# Group_03.net
KiCad netlist of a schematic drawn in EAGLE
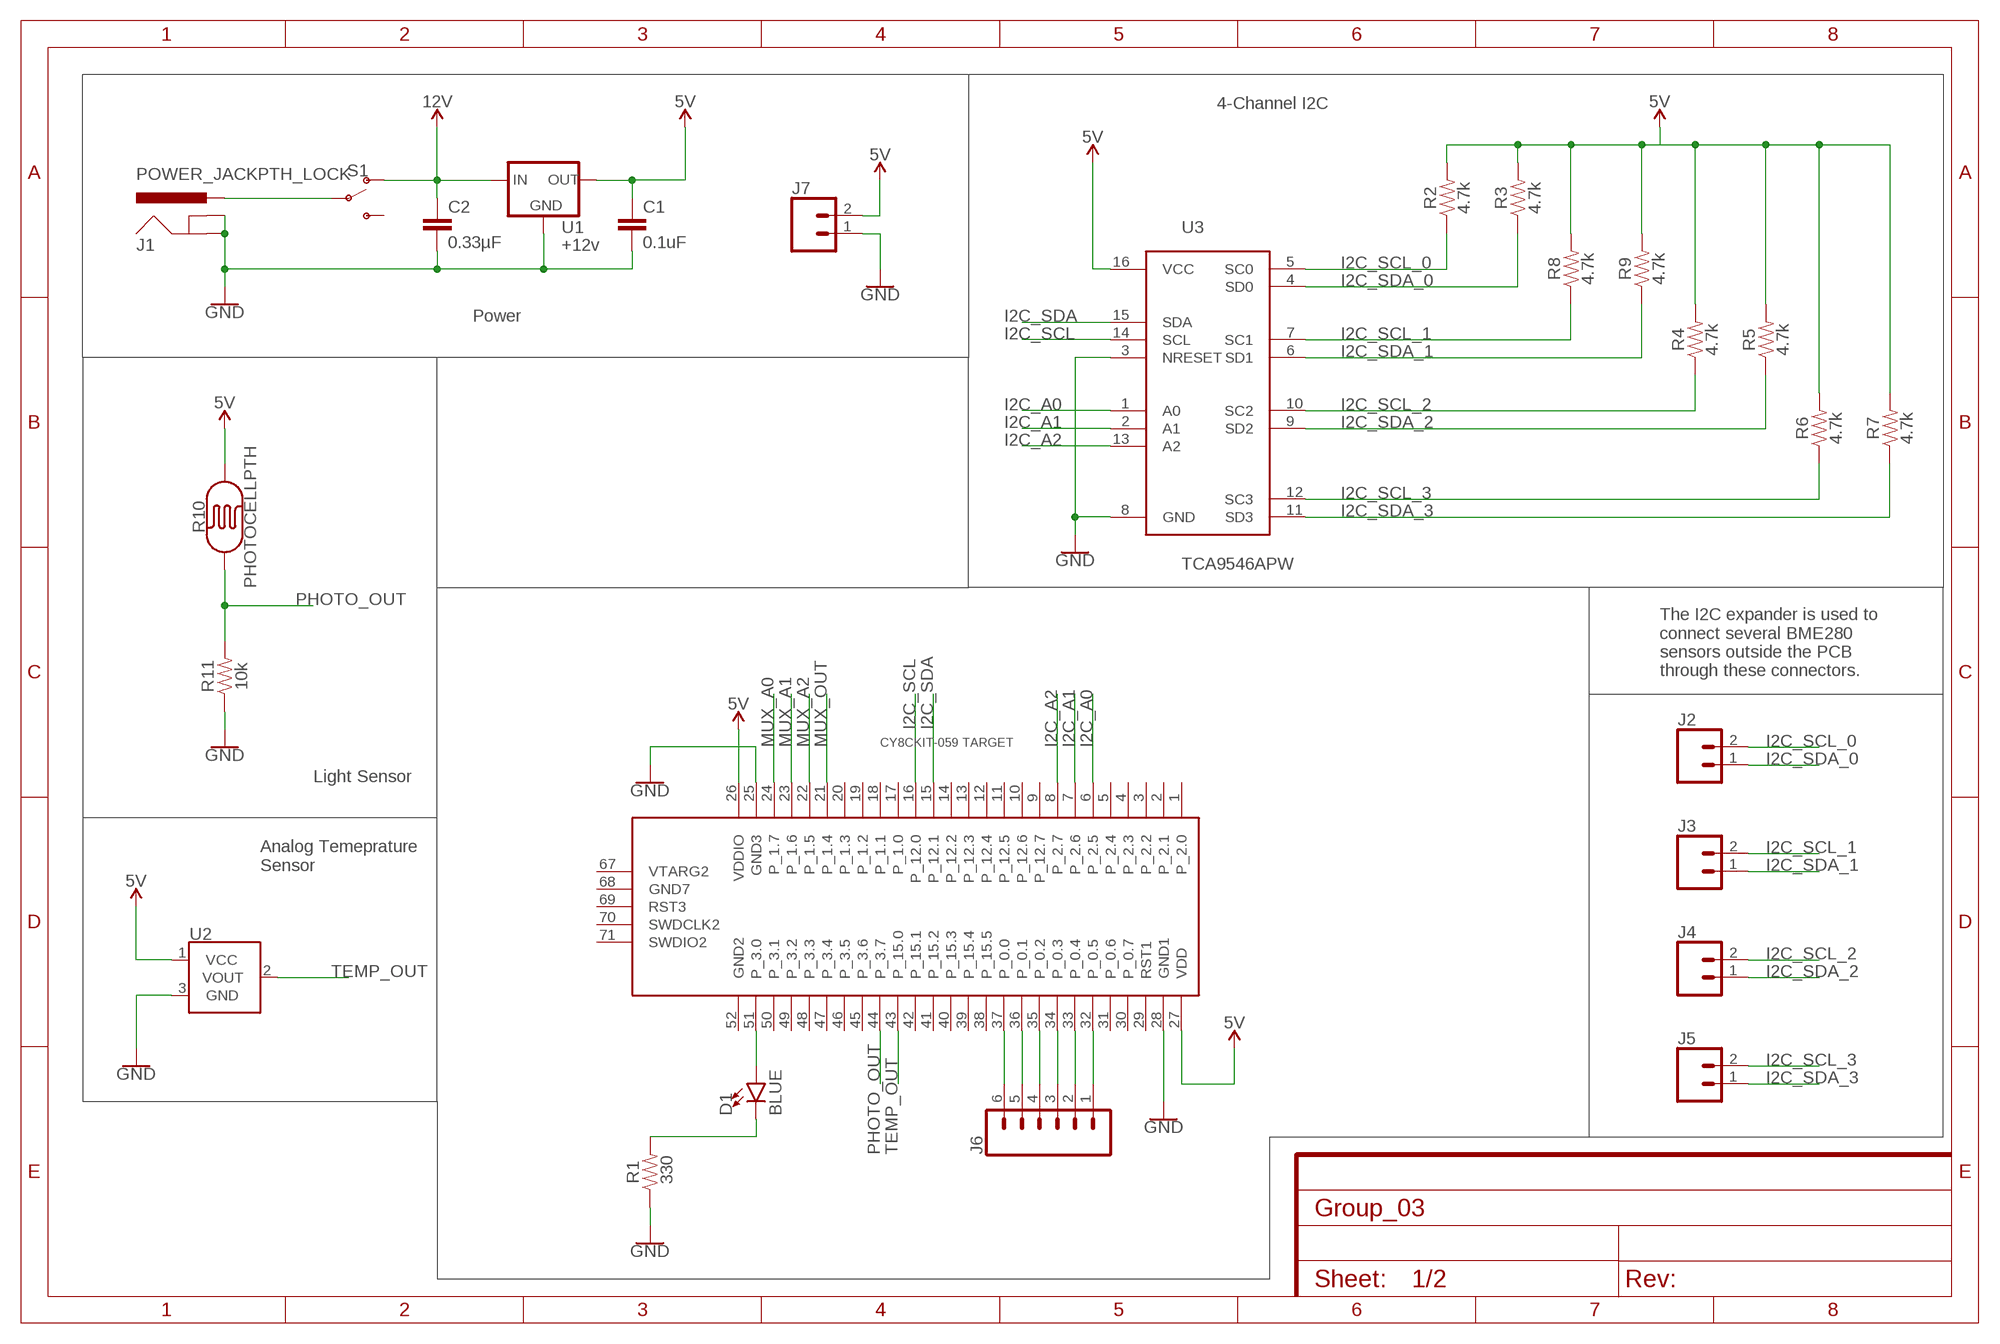
[diagram p0: schematic, sheet 1]
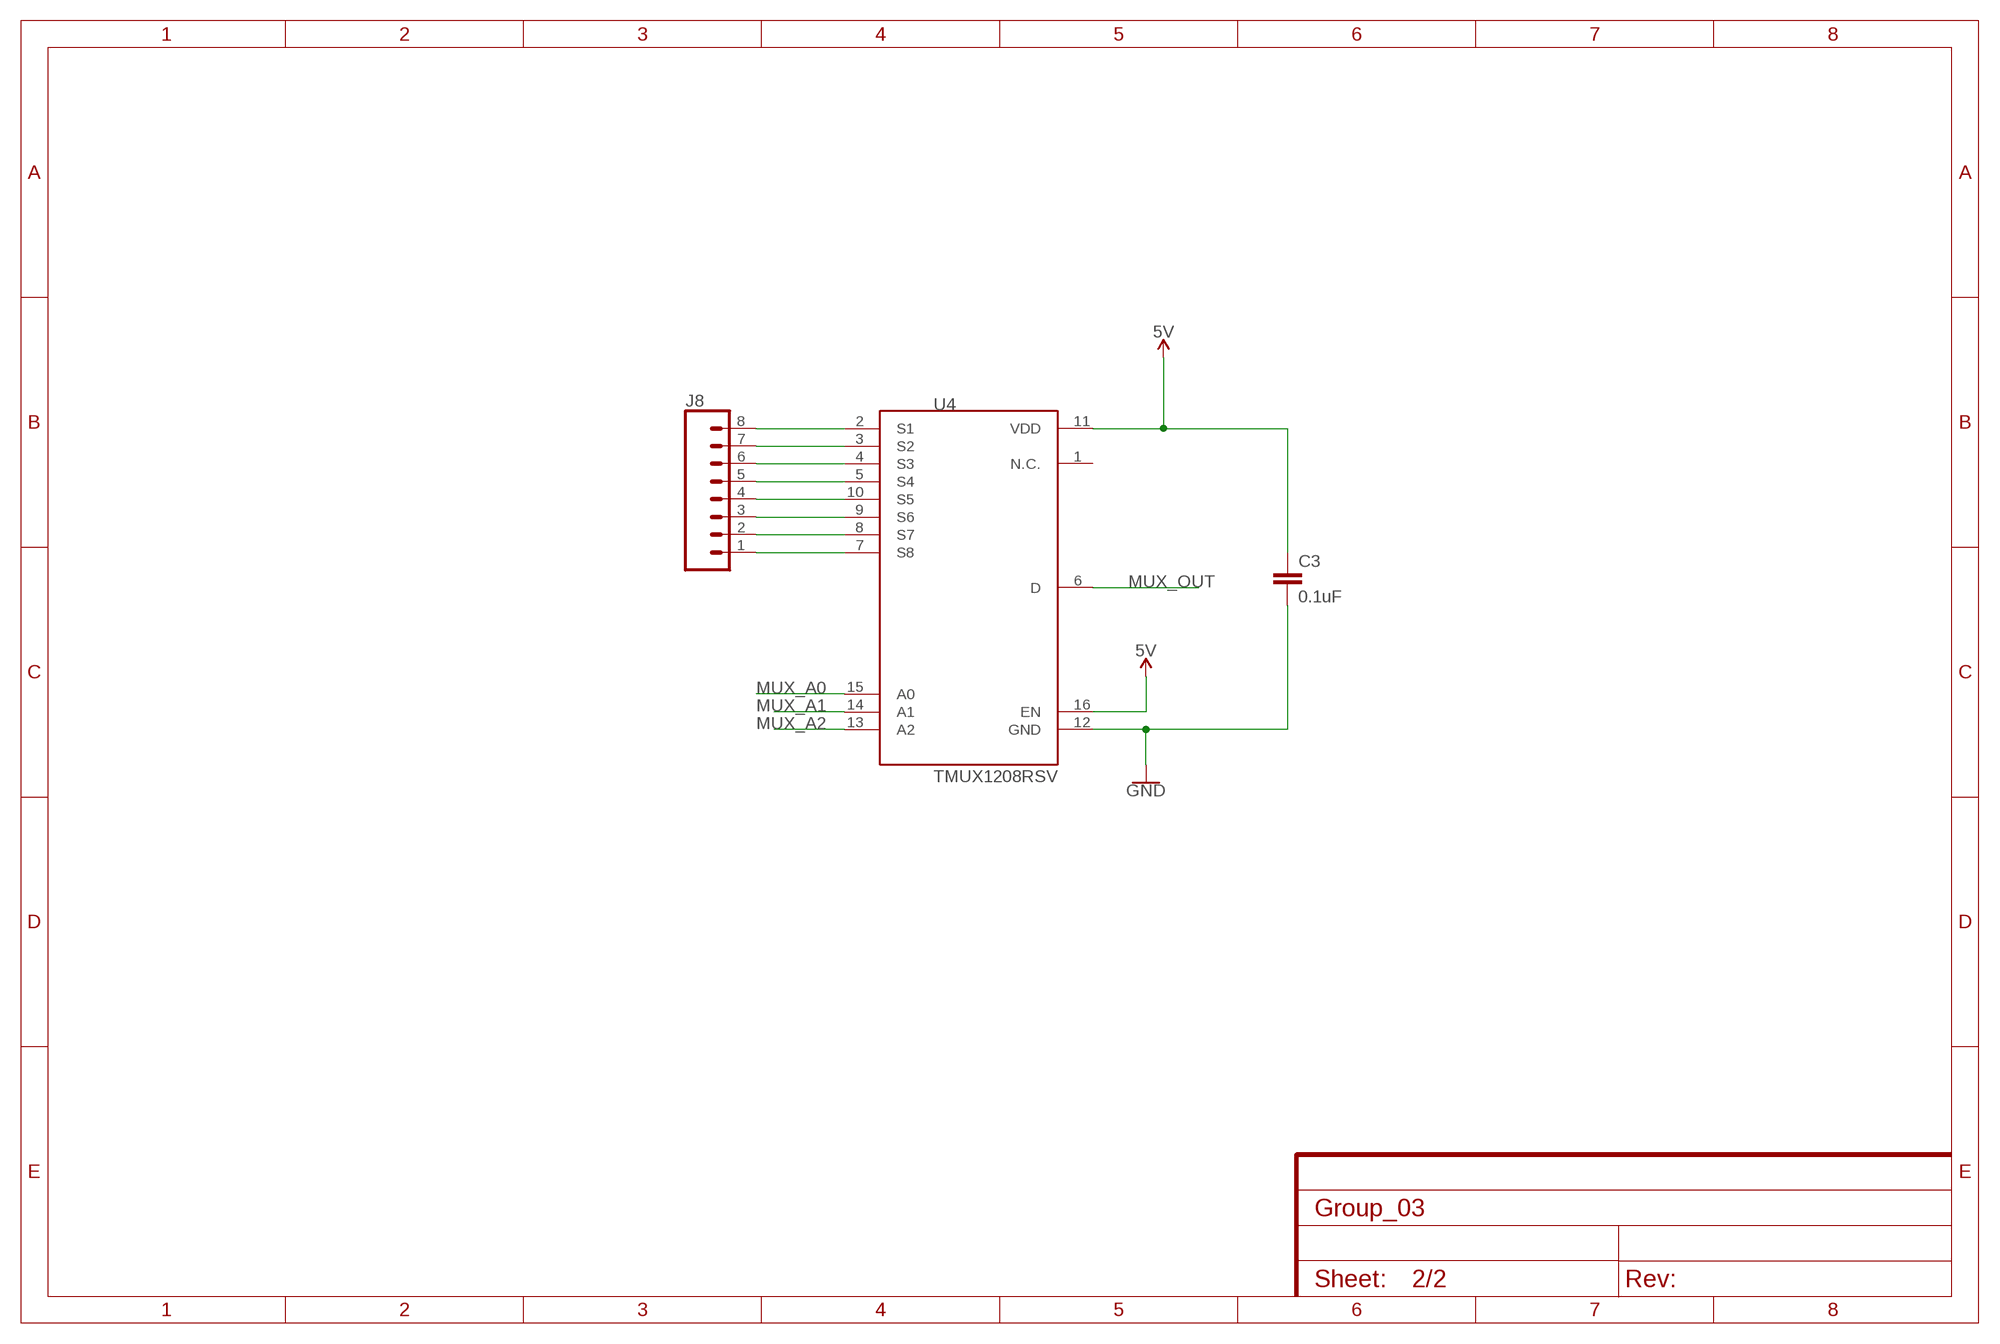
[diagram p1: schematic, sheet 2]

(export (version "E")
  (design (tool "Eeschema 10.0.6"))
  (components
    (comp (ref "C3")
      (value "0.1uF")
      (footprint "eagle-import:CAP-PTH-SMALL-KIT")
      (libsource (lib "eagle-import") (part "0.1UF-KIT-EZ-50V-20%"))
    )
    (comp (ref "J8")
      (value "CONN_08LOCK")
      (footprint "eagle-import:1X08_LOCK")
      (libsource (lib "eagle-import") (part "CONN_08LOCK"))
    )
    (comp (ref "U4")
      (value "TMUX1208RSV")
      (footprint "eagle-import:QFN16")
      (libsource (lib "eagle-import") (part "TMUX1208RSV"))
    )
    (comp (ref "C1")
      (value "0.1uF")
      (footprint "eagle-import:CAP-PTH-SMALL-KIT")
      (libsource (lib "eagle-import") (part "0.1UF-KIT-EZ-50V-20%"))
    )
    (comp (ref "C2")
      (value "0.33µF")
      (footprint "eagle-import:0805")
      (libsource (lib "eagle-import") (part "0.33UF/330NF-0805-50V-10%"))
    )
    (comp (ref "D1")
      (value "BLUE")
      (footprint "eagle-import:LED-1206")
      (libsource (lib "eagle-import") (part "LED-BLUE1206"))
    )
    (comp (ref "J1")
      (value "POWER_JACKPTH_LOCK")
      (footprint "eagle-import:POWER_JACK_PTH_LOCK")
      (libsource (lib "eagle-import") (part "POWER_JACKPTH_LOCK"))
    )
    (comp (ref "J2")
      (value "CONN_02")
      (footprint "eagle-import:1X02")
      (libsource (lib "eagle-import") (part "CONN_02"))
    )
    (comp (ref "J3")
      (value "CONN_02")
      (footprint "eagle-import:1X02")
      (libsource (lib "eagle-import") (part "CONN_02"))
    )
    (comp (ref "J4")
      (value "CONN_02")
      (footprint "eagle-import:1X02")
      (libsource (lib "eagle-import") (part "CONN_02"))
    )
    (comp (ref "J5")
      (value "CONN_02")
      (footprint "eagle-import:1X02")
      (libsource (lib "eagle-import") (part "CONN_02"))
    )
    (comp (ref "J6")
      (value "CONN_06LOCK")
      (footprint "eagle-import:1X06_LOCK")
      (libsource (lib "eagle-import") (part "CONN_06LOCK"))
    )
    (comp (ref "J7")
      (value "CONN_02")
      (footprint "eagle-import:1X02")
      (libsource (lib "eagle-import") (part "CONN_02"))
    )
    (comp (ref "R1")
      (value "330")
      (footprint "eagle-import:AXIAL-0.3")
      (libsource (lib "eagle-import") (part "RESISTORAXIAL-0.3"))
    )
    (comp (ref "R2")
      (value "4.7k")
      (footprint "eagle-import:0603")
      (libsource (lib "eagle-import") (part "4.7KOHM-0603-1/10W-1%"))
    )
    (comp (ref "R3")
      (value "4.7k")
      (footprint "eagle-import:0603")
      (libsource (lib "eagle-import") (part "4.7KOHM-0603-1/10W-1%"))
    )
    (comp (ref "R4")
      (value "4.7k")
      (footprint "eagle-import:0603")
      (libsource (lib "eagle-import") (part "4.7KOHM-0603-1/10W-1%"))
    )
    (comp (ref "R5")
      (value "4.7k")
      (footprint "eagle-import:0603")
      (libsource (lib "eagle-import") (part "4.7KOHM-0603-1/10W-1%"))
    )
    (comp (ref "R6")
      (value "4.7k")
      (footprint "eagle-import:0603")
      (libsource (lib "eagle-import") (part "4.7KOHM-0603-1/10W-1%"))
    )
    (comp (ref "R7")
      (value "4.7k")
      (footprint "eagle-import:0603")
      (libsource (lib "eagle-import") (part "4.7KOHM-0603-1/10W-1%"))
    )
    (comp (ref "R8")
      (value "4.7k")
      (footprint "eagle-import:0603")
      (libsource (lib "eagle-import") (part "4.7KOHM-0603-1/10W-1%"))
    )
    (comp (ref "R9")
      (value "4.7k")
      (footprint "eagle-import:0603")
      (libsource (lib "eagle-import") (part "4.7KOHM-0603-1/10W-1%"))
    )
    (comp (ref "R10")
      (value "PHOTOCELLPTH")
      (footprint "eagle-import:PHOTOCELL")
      (libsource (lib "eagle-import") (part "PHOTOCELLPTH"))
    )
    (comp (ref "R11")
      (value "10k")
      (footprint "eagle-import:0603")
      (libsource (lib "eagle-import") (part "10KOHM-0603-1/10W-1%"))
    )
    (comp (ref "S1")
      (value "SWITCH-SPDT-PTH-11.6X4.0MM")
      (footprint "eagle-import:SWITCH_SPDT_PTH_11.6X4.0MM")
      (libsource (lib "eagle-import") (part "SWITCH-SPDT-PTH-11.6X4.0MM"))
    )
    (comp (ref "U$1")
      (value "CY8CKIT-059_TARGET")
      (footprint "eagle-import:CY8CKIT-059_TARGET")
      (libsource (lib "eagle-import") (part "CY8CKIT-059_TARGET"))
    )
    (comp (ref "U1")
      (value "+12v")
      (footprint "eagle-import:TO-252")
      (libsource (lib "eagle-import") (part "V_REG_78XX7812"))
    )
    (comp (ref "U2")
      (value "TMP36GT9")
      (footprint "eagle-import:TO-92")
      (libsource (lib "eagle-import") (part "TMP36GT9"))
    )
    (comp (ref "U3")
      (value "TCA9546APW")
      (footprint "eagle-import:TSSOP16")
      (libsource (lib "eagle-import") (part "TCA9546APW"))
    )
  )
  (nets
    (net (code "1") (name "5V") (class "Default")
      (node (ref "C1") (pin "1") (pinfunction "1_1") (pintype "passive"))
      (node (ref "C3") (pin "1") (pinfunction "1_1") (pintype "passive"))
      (node (ref "J7") (pin "2") (pinfunction "2_2") (pintype "passive"))
      (node (ref "R10") (pin "2") (pinfunction "P$2_2") (pintype "bidirectional"))
      (node (ref "R2") (pin "2") (pinfunction "2_2") (pintype "passive"))
      (node (ref "R3") (pin "2") (pinfunction "2_2") (pintype "passive"))
      (node (ref "R4") (pin "2") (pinfunction "2_2") (pintype "passive"))
      (node (ref "R5") (pin "2") (pinfunction "2_2") (pintype "passive"))
      (node (ref "R6") (pin "2") (pinfunction "2_2") (pintype "passive"))
      (node (ref "R7") (pin "2") (pinfunction "2_2") (pintype "passive"))
      (node (ref "R8") (pin "2") (pinfunction "2_2") (pintype "passive"))
      (node (ref "R9") (pin "2") (pinfunction "2_2") (pintype "passive"))
      (node (ref "U$1") (pin "26") (pinfunction "VDDIO_26") (pintype "bidirectional"))
      (node (ref "U$1") (pin "27") (pinfunction "VDD_27") (pintype "bidirectional"))
      (node (ref "U1") (pin "2") (pinfunction "OUT_2") (pintype "passive"))
      (node (ref "U2") (pin "1") (pinfunction "VCC_1") (pintype "bidirectional"))
      (node (ref "U3") (pin "16") (pinfunction "VCC_16") (pintype "bidirectional"))
      (node (ref "U4") (pin "11") (pinfunction "VDD_11") (pintype "bidirectional"))
      (node (ref "U4") (pin "16") (pinfunction "EN_16") (pintype "bidirectional"))
    )
    (net (code "2") (name "12V") (class "Default")
      (node (ref "C2") (pin "1") (pinfunction "1_1") (pintype "passive"))
      (node (ref "S1") (pin "1") (pinfunction "O_1") (pintype "passive"))
      (node (ref "U1") (pin "1") (pinfunction "IN_1") (pintype "input"))
    )
    (net (code "3") (name "GND") (class "Default")
      (node (ref "C1") (pin "2") (pinfunction "2_2") (pintype "passive"))
      (node (ref "C2") (pin "2") (pinfunction "2_2") (pintype "passive"))
      (node (ref "C3") (pin "2") (pinfunction "2_2") (pintype "passive"))
      (node (ref "J1") (pin "GND") (pinfunction "GND_GND") (pintype "bidirectional"))
      (node (ref "J1") (pin "GNDBREAK") (pinfunction "GNDBREAK_GNDBREAK") (pintype "bidirectional"))
      (node (ref "J7") (pin "1") (pinfunction "1_1") (pintype "passive"))
      (node (ref "R1") (pin "P$1") (pinfunction "1_P$1") (pintype "passive"))
      (node (ref "R11") (pin "1") (pinfunction "1_1") (pintype "passive"))
      (node (ref "U$1") (pin "25") (pinfunction "GND3_25") (pintype "bidirectional"))
      (node (ref "U$1") (pin "28") (pinfunction "GND1_28") (pintype "bidirectional"))
      (node (ref "U1") (pin "3") (pinfunction "GND_3") (pintype "input"))
      (node (ref "U2") (pin "3") (pinfunction "GND_3") (pintype "bidirectional"))
      (node (ref "U3") (pin "3") (pinfunction "NRESET_3") (pintype "bidirectional"))
      (node (ref "U3") (pin "8") (pinfunction "GND_8") (pintype "bidirectional"))
      (node (ref "U4") (pin "12") (pinfunction "GND_12") (pintype "bidirectional"))
    )
    (net (code "4") (name "I2C_A0") (class "Default")
      (node (ref "U$1") (pin "6") (pinfunction "P_2.5_6") (pintype "bidirectional"))
      (node (ref "U3") (pin "1") (pinfunction "A0_1") (pintype "bidirectional"))
    )
    (net (code "5") (name "I2C_A1") (class "Default")
      (node (ref "U$1") (pin "7") (pinfunction "P_2.6_7") (pintype "bidirectional"))
      (node (ref "U3") (pin "2") (pinfunction "A1_2") (pintype "bidirectional"))
    )
    (net (code "6") (name "I2C_A2") (class "Default")
      (node (ref "U$1") (pin "8") (pinfunction "P_2.7_8") (pintype "bidirectional"))
      (node (ref "U3") (pin "13") (pinfunction "A2_13") (pintype "bidirectional"))
    )
    (net (code "7") (name "I2C_SCL") (class "Default")
      (node (ref "U$1") (pin "16") (pinfunction "P_12.0_16") (pintype "bidirectional"))
      (node (ref "U3") (pin "14") (pinfunction "SCL_14") (pintype "bidirectional"))
    )
    (net (code "8") (name "I2C_SCL_0") (class "Default")
      (node (ref "J2") (pin "2") (pinfunction "2_2") (pintype "passive"))
      (node (ref "R2") (pin "1") (pinfunction "1_1") (pintype "passive"))
      (node (ref "U3") (pin "5") (pinfunction "SC0_5") (pintype "bidirectional"))
    )
    (net (code "9") (name "I2C_SCL_1") (class "Default")
      (node (ref "J3") (pin "2") (pinfunction "2_2") (pintype "passive"))
      (node (ref "R8") (pin "1") (pinfunction "1_1") (pintype "passive"))
      (node (ref "U3") (pin "7") (pinfunction "SC1_7") (pintype "bidirectional"))
    )
    (net (code "10") (name "I2C_SCL_2") (class "Default")
      (node (ref "J4") (pin "2") (pinfunction "2_2") (pintype "passive"))
      (node (ref "R4") (pin "1") (pinfunction "1_1") (pintype "passive"))
      (node (ref "U3") (pin "10") (pinfunction "SC2_10") (pintype "bidirectional"))
    )
    (net (code "11") (name "I2C_SCL_3") (class "Default")
      (node (ref "J5") (pin "2") (pinfunction "2_2") (pintype "passive"))
      (node (ref "R6") (pin "1") (pinfunction "1_1") (pintype "passive"))
      (node (ref "U3") (pin "12") (pinfunction "SC3_12") (pintype "bidirectional"))
    )
    (net (code "12") (name "I2C_SDA") (class "Default")
      (node (ref "U$1") (pin "15") (pinfunction "P_12.1_15") (pintype "bidirectional"))
      (node (ref "U3") (pin "15") (pinfunction "SDA_15") (pintype "bidirectional"))
    )
    (net (code "13") (name "I2C_SDA_0") (class "Default")
      (node (ref "J2") (pin "1") (pinfunction "1_1") (pintype "passive"))
      (node (ref "R3") (pin "1") (pinfunction "1_1") (pintype "passive"))
      (node (ref "U3") (pin "4") (pinfunction "SD0_4") (pintype "bidirectional"))
    )
    (net (code "14") (name "I2C_SDA_1") (class "Default")
      (node (ref "J3") (pin "1") (pinfunction "1_1") (pintype "passive"))
      (node (ref "R9") (pin "1") (pinfunction "1_1") (pintype "passive"))
      (node (ref "U3") (pin "6") (pinfunction "SD1_6") (pintype "bidirectional"))
    )
    (net (code "15") (name "I2C_SDA_2") (class "Default")
      (node (ref "J4") (pin "1") (pinfunction "1_1") (pintype "passive"))
      (node (ref "R5") (pin "1") (pinfunction "1_1") (pintype "passive"))
      (node (ref "U3") (pin "9") (pinfunction "SD2_9") (pintype "bidirectional"))
    )
    (net (code "16") (name "I2C_SDA_3") (class "Default")
      (node (ref "J5") (pin "1") (pinfunction "1_1") (pintype "passive"))
      (node (ref "R7") (pin "1") (pinfunction "1_1") (pintype "passive"))
      (node (ref "U3") (pin "11") (pinfunction "SD3_11") (pintype "bidirectional"))
    )
    (net (code "17") (name "MUX_A0") (class "Default")
      (node (ref "U$1") (pin "24") (pinfunction "P_1.7_24") (pintype "bidirectional"))
      (node (ref "U4") (pin "15") (pinfunction "A0_15") (pintype "bidirectional"))
    )
    (net (code "18") (name "MUX_A1") (class "Default")
      (node (ref "U$1") (pin "23") (pinfunction "P_1.6_23") (pintype "bidirectional"))
      (node (ref "U4") (pin "14") (pinfunction "A1_14") (pintype "bidirectional"))
    )
    (net (code "19") (name "MUX_A2") (class "Default")
      (node (ref "U$1") (pin "22") (pinfunction "P_1.5_22") (pintype "bidirectional"))
      (node (ref "U4") (pin "13") (pinfunction "A2_13") (pintype "bidirectional"))
    )
    (net (code "20") (name "MUX_OUT") (class "Default")
      (node (ref "U$1") (pin "21") (pinfunction "P_1.4_21") (pintype "bidirectional"))
      (node (ref "U4") (pin "6") (pinfunction "D_6") (pintype "bidirectional"))
    )
    (net (code "21") (name "Net-(R1-2)") (class "Default")
      (node (ref "D1") (pin "C") (pinfunction "C_C") (pintype "passive"))
      (node (ref "R1") (pin "P$2") (pinfunction "2_P$2") (pintype "passive"))
    )
    (net (code "22") (name "Net-(S1-P)") (class "Default")
      (node (ref "J1") (pin "PWR") (pinfunction "PWR_PWR") (pintype "bidirectional"))
      (node (ref "S1") (pin "2") (pinfunction "P_2") (pintype "passive"))
    )
    (net (code "23") (name "Net-(U$1-P_0.0)") (class "Default")
      (node (ref "J6") (pin "6") (pinfunction "6_6") (pintype "passive"))
      (node (ref "U$1") (pin "37") (pinfunction "P_0.0_37") (pintype "bidirectional"))
    )
    (net (code "24") (name "Net-(U$1-P_0.1)") (class "Default")
      (node (ref "J6") (pin "5") (pinfunction "5_5") (pintype "passive"))
      (node (ref "U$1") (pin "36") (pinfunction "P_0.1_36") (pintype "bidirectional"))
    )
    (net (code "25") (name "Net-(U$1-P_0.2)") (class "Default")
      (node (ref "J6") (pin "4") (pinfunction "4_4") (pintype "passive"))
      (node (ref "U$1") (pin "35") (pinfunction "P_0.2_35") (pintype "bidirectional"))
    )
    (net (code "26") (name "Net-(U$1-P_0.3)") (class "Default")
      (node (ref "J6") (pin "3") (pinfunction "3_3") (pintype "passive"))
      (node (ref "U$1") (pin "34") (pinfunction "P_0.3_34") (pintype "bidirectional"))
    )
    (net (code "27") (name "Net-(U$1-P_0.4)") (class "Default")
      (node (ref "J6") (pin "2") (pinfunction "2_2") (pintype "passive"))
      (node (ref "U$1") (pin "33") (pinfunction "P_0.4_33") (pintype "bidirectional"))
    )
    (net (code "28") (name "Net-(U$1-P_0.5)") (class "Default")
      (node (ref "J6") (pin "1") (pinfunction "1_1") (pintype "passive"))
      (node (ref "U$1") (pin "32") (pinfunction "P_0.5_32") (pintype "bidirectional"))
    )
    (net (code "29") (name "Net-(U$1-P_3.0)") (class "Default")
      (node (ref "D1") (pin "A") (pinfunction "A_A") (pintype "passive"))
      (node (ref "U$1") (pin "51") (pinfunction "P_3.0_51") (pintype "bidirectional"))
    )
    (net (code "30") (name "Net-(U4-S1)") (class "Default")
      (node (ref "J8") (pin "8") (pinfunction "8_8") (pintype "passive"))
      (node (ref "U4") (pin "2") (pinfunction "S1_2") (pintype "bidirectional"))
    )
    (net (code "31") (name "Net-(U4-S2)") (class "Default")
      (node (ref "J8") (pin "7") (pinfunction "7_7") (pintype "passive"))
      (node (ref "U4") (pin "3") (pinfunction "S2_3") (pintype "bidirectional"))
    )
    (net (code "32") (name "Net-(U4-S3)") (class "Default")
      (node (ref "J8") (pin "6") (pinfunction "6_6") (pintype "passive"))
      (node (ref "U4") (pin "4") (pinfunction "S3_4") (pintype "bidirectional"))
    )
    (net (code "33") (name "Net-(U4-S4)") (class "Default")
      (node (ref "J8") (pin "5") (pinfunction "5_5") (pintype "passive"))
      (node (ref "U4") (pin "5") (pinfunction "S4_5") (pintype "bidirectional"))
    )
    (net (code "34") (name "Net-(U4-S5)") (class "Default")
      (node (ref "J8") (pin "4") (pinfunction "4_4") (pintype "passive"))
      (node (ref "U4") (pin "10") (pinfunction "S5_10") (pintype "bidirectional"))
    )
    (net (code "35") (name "Net-(U4-S6)") (class "Default")
      (node (ref "J8") (pin "3") (pinfunction "3_3") (pintype "passive"))
      (node (ref "U4") (pin "9") (pinfunction "S6_9") (pintype "bidirectional"))
    )
    (net (code "36") (name "Net-(U4-S7)") (class "Default")
      (node (ref "J8") (pin "2") (pinfunction "2_2") (pintype "passive"))
      (node (ref "U4") (pin "8") (pinfunction "S7_8") (pintype "bidirectional"))
    )
    (net (code "37") (name "Net-(U4-S8)") (class "Default")
      (node (ref "J8") (pin "1") (pinfunction "1_1") (pintype "passive"))
      (node (ref "U4") (pin "7") (pinfunction "S8_7") (pintype "bidirectional"))
    )
    (net (code "38") (name "PHOTO_OUT") (class "Default")
      (node (ref "R10") (pin "1") (pinfunction "P$1_1") (pintype "bidirectional"))
      (node (ref "R11") (pin "2") (pinfunction "2_2") (pintype "passive"))
      (node (ref "U$1") (pin "44") (pinfunction "P_3.7_44") (pintype "bidirectional"))
    )
    (net (code "39") (name "TEMP_OUT") (class "Default")
      (node (ref "U$1") (pin "43") (pinfunction "P_15.0_43") (pintype "bidirectional"))
      (node (ref "U2") (pin "2") (pinfunction "VOUT_2") (pintype "bidirectional"))
    )
    (net (code "40") (name "unconnected-(S1-S-Pad3)") (class "Default")
      (node (ref "S1") (pin "3") (pinfunction "S_3") (pintype "passive"))
    )
    (net (code "41") (name "unconnected-(U$1-GND2-Pad52)") (class "Default")
      (node (ref "U$1") (pin "52") (pinfunction "GND2_52") (pintype "bidirectional"))
    )
    (net (code "42") (name "unconnected-(U$1-GND7-Pad68)") (class "Default")
      (node (ref "U$1") (pin "68") (pinfunction "GND7_68") (pintype "bidirectional"))
    )
    (net (code "43") (name "unconnected-(U$1-P_0.6-Pad31)") (class "Default")
      (node (ref "U$1") (pin "31") (pinfunction "P_0.6_31") (pintype "bidirectional"))
    )
    (net (code "44") (name "unconnected-(U$1-P_0.7-Pad30)") (class "Default")
      (node (ref "U$1") (pin "30") (pinfunction "P_0.7_30") (pintype "bidirectional"))
    )
    (net (code "45") (name "unconnected-(U$1-P_1.0-Pad17)") (class "Default")
      (node (ref "U$1") (pin "17") (pinfunction "P_1.0_17") (pintype "bidirectional"))
    )
    (net (code "46") (name "unconnected-(U$1-P_1.1-Pad18)") (class "Default")
      (node (ref "U$1") (pin "18") (pinfunction "P_1.1_18") (pintype "bidirectional"))
    )
    (net (code "47") (name "unconnected-(U$1-P_1.2-Pad19)") (class "Default")
      (node (ref "U$1") (pin "19") (pinfunction "P_1.2_19") (pintype "bidirectional"))
    )
    (net (code "48") (name "unconnected-(U$1-P_1.3-Pad20)") (class "Default")
      (node (ref "U$1") (pin "20") (pinfunction "P_1.3_20") (pintype "bidirectional"))
    )
    (net (code "49") (name "unconnected-(U$1-P_2.0-Pad1)") (class "Default")
      (node (ref "U$1") (pin "1") (pinfunction "P_2.0_1") (pintype "bidirectional"))
    )
    (net (code "50") (name "unconnected-(U$1-P_2.1-Pad2)") (class "Default")
      (node (ref "U$1") (pin "2") (pinfunction "P_2.1_2") (pintype "bidirectional"))
    )
    (net (code "51") (name "unconnected-(U$1-P_2.2-Pad3)") (class "Default")
      (node (ref "U$1") (pin "3") (pinfunction "P_2.2_3") (pintype "bidirectional"))
    )
    (net (code "52") (name "unconnected-(U$1-P_2.3-Pad4)") (class "Default")
      (node (ref "U$1") (pin "4") (pinfunction "P_2.3_4") (pintype "bidirectional"))
    )
    (net (code "53") (name "unconnected-(U$1-P_2.4-Pad5)") (class "Default")
      (node (ref "U$1") (pin "5") (pinfunction "P_2.4_5") (pintype "bidirectional"))
    )
    (net (code "54") (name "unconnected-(U$1-P_3.1-Pad50)") (class "Default")
      (node (ref "U$1") (pin "50") (pinfunction "P_3.1_50") (pintype "bidirectional"))
    )
    (net (code "55") (name "unconnected-(U$1-P_3.2-Pad49)") (class "Default")
      (node (ref "U$1") (pin "49") (pinfunction "P_3.2_49") (pintype "bidirectional"))
    )
    (net (code "56") (name "unconnected-(U$1-P_3.3-Pad48)") (class "Default")
      (node (ref "U$1") (pin "48") (pinfunction "P_3.3_48") (pintype "bidirectional"))
    )
    (net (code "57") (name "unconnected-(U$1-P_3.4-Pad47)") (class "Default")
      (node (ref "U$1") (pin "47") (pinfunction "P_3.4_47") (pintype "bidirectional"))
    )
    (net (code "58") (name "unconnected-(U$1-P_3.5-Pad46)") (class "Default")
      (node (ref "U$1") (pin "46") (pinfunction "P_3.5_46") (pintype "bidirectional"))
    )
    (net (code "59") (name "unconnected-(U$1-P_3.6-Pad45)") (class "Default")
      (node (ref "U$1") (pin "45") (pinfunction "P_3.6_45") (pintype "bidirectional"))
    )
    (net (code "60") (name "unconnected-(U$1-P_12.2-Pad14)") (class "Default")
      (node (ref "U$1") (pin "14") (pinfunction "P_12.2_14") (pintype "bidirectional"))
    )
    (net (code "61") (name "unconnected-(U$1-P_12.3-Pad13)") (class "Default")
      (node (ref "U$1") (pin "13") (pinfunction "P_12.3_13") (pintype "bidirectional"))
    )
    (net (code "62") (name "unconnected-(U$1-P_12.4-Pad12)") (class "Default")
      (node (ref "U$1") (pin "12") (pinfunction "P_12.4_12") (pintype "bidirectional"))
    )
    (net (code "63") (name "unconnected-(U$1-P_12.5-Pad11)") (class "Default")
      (node (ref "U$1") (pin "11") (pinfunction "P_12.5_11") (pintype "bidirectional"))
    )
    (net (code "64") (name "unconnected-(U$1-P_12.6-Pad10)") (class "Default")
      (node (ref "U$1") (pin "10") (pinfunction "P_12.6_10") (pintype "bidirectional"))
    )
    (net (code "65") (name "unconnected-(U$1-P_12.7-Pad9)") (class "Default")
      (node (ref "U$1") (pin "9") (pinfunction "P_12.7_9") (pintype "bidirectional"))
    )
    (net (code "66") (name "unconnected-(U$1-P_15.1-Pad42)") (class "Default")
      (node (ref "U$1") (pin "42") (pinfunction "P_15.1_42") (pintype "bidirectional"))
    )
    (net (code "67") (name "unconnected-(U$1-P_15.2-Pad41)") (class "Default")
      (node (ref "U$1") (pin "41") (pinfunction "P_15.2_41") (pintype "bidirectional"))
    )
    (net (code "68") (name "unconnected-(U$1-P_15.3-Pad40)") (class "Default")
      (node (ref "U$1") (pin "40") (pinfunction "P_15.3_40") (pintype "bidirectional"))
    )
    (net (code "69") (name "unconnected-(U$1-P_15.4-Pad39)") (class "Default")
      (node (ref "U$1") (pin "39") (pinfunction "P_15.4_39") (pintype "bidirectional"))
    )
    (net (code "70") (name "unconnected-(U$1-P_15.5-Pad38)") (class "Default")
      (node (ref "U$1") (pin "38") (pinfunction "P_15.5_38") (pintype "bidirectional"))
    )
    (net (code "71") (name "unconnected-(U$1-RST1-Pad29)") (class "Default")
      (node (ref "U$1") (pin "29") (pinfunction "RST1_29") (pintype "bidirectional"))
    )
    (net (code "72") (name "unconnected-(U$1-RST3-Pad69)") (class "Default")
      (node (ref "U$1") (pin "69") (pinfunction "RST3_69") (pintype "bidirectional"))
    )
    (net (code "73") (name "unconnected-(U$1-SWDCLK2-Pad70)") (class "Default")
      (node (ref "U$1") (pin "70") (pinfunction "SWDCLK2_70") (pintype "bidirectional"))
    )
    (net (code "74") (name "unconnected-(U$1-SWDIO2-Pad71)") (class "Default")
      (node (ref "U$1") (pin "71") (pinfunction "SWDIO2_71") (pintype "bidirectional"))
    )
    (net (code "75") (name "unconnected-(U$1-VTARG2-Pad67)") (class "Default")
      (node (ref "U$1") (pin "67") (pinfunction "VTARG2_67") (pintype "bidirectional"))
    )
    (net (code "76") (name "unconnected-(U4-N.C.-Pad1)") (class "Default")
      (node (ref "U4") (pin "1") (pinfunction "N.C._1") (pintype "bidirectional"))
    )
  )
)
